# STM32_MACH3-Interfaceboard.net
KiCad netlist of a schematic drawn in EAGLE
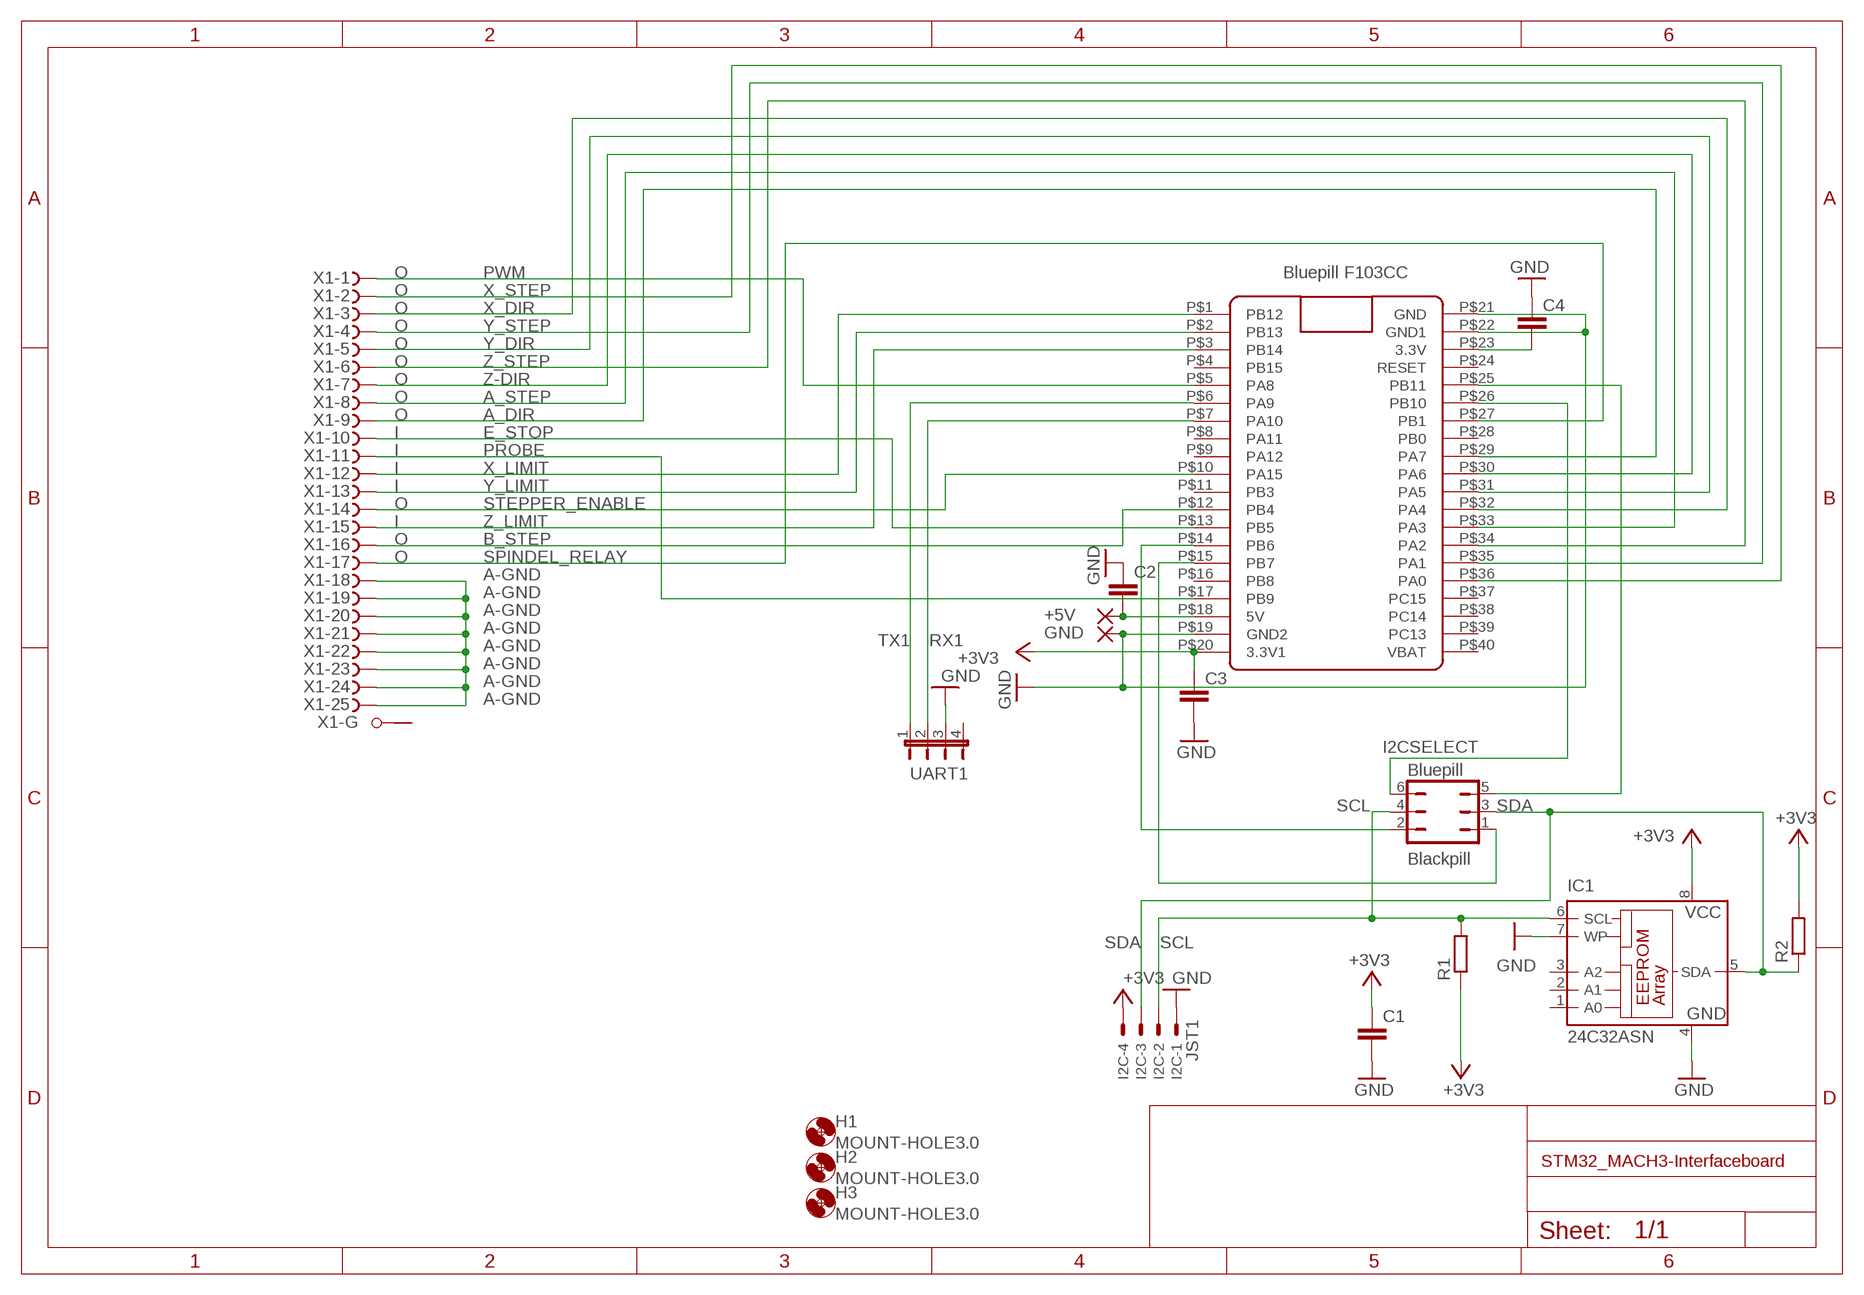
[diagram p0: schematic, sheet 1]

(export (version "E")
  (design (tool "Eeschema 10.0.6"))
  (components
    (comp (ref "+5V")
      (value "2,54/1,0")
      (footprint "eagle-import:2,54_1,0")
      (libsource (lib "eagle-import") (part "2,54/1,0"))
    )
    (comp (ref "C1")
      (value "C-EUC0805")
      (footprint "eagle-import:C0805")
      (libsource (lib "eagle-import") (part "C-EUC0805"))
    )
    (comp (ref "C2")
      (value "C-EUC0805")
      (footprint "eagle-import:C0805")
      (libsource (lib "eagle-import") (part "C-EUC0805"))
    )
    (comp (ref "C3")
      (value "C-EUC0805")
      (footprint "eagle-import:C0805")
      (libsource (lib "eagle-import") (part "C-EUC0805"))
    )
    (comp (ref "C4")
      (value "C-EUC0805")
      (footprint "eagle-import:C0805")
      (libsource (lib "eagle-import") (part "C-EUC0805"))
    )
    (comp (ref "GND")
      (value "2,54/1,0")
      (footprint "eagle-import:2,54_1,0")
      (libsource (lib "eagle-import") (part "2,54/1,0"))
    )
    (comp (ref "H1")
      (value "MOUNT-HOLE3.0")
      (footprint "eagle-import:3,0")
      (libsource (lib "eagle-import") (part "MOUNT-HOLE3.0"))
    )
    (comp (ref "H2")
      (value "MOUNT-HOLE3.0")
      (footprint "eagle-import:3,0")
      (libsource (lib "eagle-import") (part "MOUNT-HOLE3.0"))
    )
    (comp (ref "H3")
      (value "MOUNT-HOLE3.0")
      (footprint "eagle-import:3,0")
      (libsource (lib "eagle-import") (part "MOUNT-HOLE3.0"))
    )
    (comp (ref "I2C")
      (value "JST1")
      (footprint "eagle-import:JST-XH-04-PACKAGE-LONG-PAD")
      (libsource (lib "eagle-import") (part "JST-XH-04-PIN-LONG-PAD"))
    )
    (comp (ref "I2CSELECT")
      (value "JP3Q")
      (footprint "eagle-import:JP3Q")
      (libsource (lib "eagle-import") (part "JP3Q"))
    )
    (comp (ref "IC1")
      (value "24C32ASN")
      (footprint "eagle-import:SO-08")
      (fields (field (name "MPN") "IS24C32A-2GLI"))
      (libsource (lib "eagle-import") (part "24SNC32A"))
    )
    (comp (ref "R1")
      (value "R-EU_R0805")
      (footprint "eagle-import:R0805")
      (libsource (lib "eagle-import") (part "R-EU_R0805"))
    )
    (comp (ref "R2")
      (value "R-EU_R0805")
      (footprint "eagle-import:R0805")
      (libsource (lib "eagle-import") (part "R-EU_R0805"))
    )
    (comp (ref "U$1")
      (value "BLUE_PILL")
      (footprint "eagle-import:BLUE_PILL")
      (libsource (lib "eagle-import") (part "BLUE_PILL"))
    )
    (comp (ref "UART1")
      (value "JP4E")
      (footprint "eagle-import:JP4")
      (libsource (lib "eagle-import") (part "JP4E"))
    )
    (comp (ref "X1")
      (value "F25HPS")
      (footprint "eagle-import:F25HP")
      (libsource (lib "eagle-import") (part "F25HPS"))
    )
  )
  (nets
    (net (code "1") (name "+3V3") (class "Default")
      (node (ref "C1") (pin "1") (pinfunction "1_1") (pintype "passive"))
      (node (ref "C3") (pin "1") (pinfunction "1_1") (pintype "passive"))
      (node (ref "I2C") (pin "4") (pinfunction "S_4") (pintype "passive"))
      (node (ref "IC1") (pin "8") (pinfunction "VCC_8") (pintype "power_in"))
      (node (ref "R1") (pin "1") (pinfunction "1_1") (pintype "passive"))
      (node (ref "R2") (pin "2") (pinfunction "2_2") (pintype "passive"))
      (node (ref "U$1") (pin "P$20") (pinfunction "3.3V1_P$20") (pintype "bidirectional"))
    )
    (net (code "2") (name "/A-GND") (class "Default")
      (node (ref "X1") (pin "18") (pinfunction "F_18") (pintype "passive"))
      (node (ref "X1") (pin "19") (pinfunction "F_19") (pintype "passive"))
      (node (ref "X1") (pin "20") (pinfunction "F_20") (pintype "passive"))
      (node (ref "X1") (pin "21") (pinfunction "F_21") (pintype "passive"))
      (node (ref "X1") (pin "22") (pinfunction "F_22") (pintype "passive"))
      (node (ref "X1") (pin "23") (pinfunction "F_23") (pintype "passive"))
      (node (ref "X1") (pin "24") (pinfunction "F_24") (pintype "passive"))
      (node (ref "X1") (pin "25") (pinfunction "F_25") (pintype "passive"))
    )
    (net (code "3") (name "/A_DIR") (class "Default")
      (node (ref "U$1") (pin "P$29") (pinfunction "PA7_P$29") (pintype "bidirectional"))
      (node (ref "X1") (pin "9") (pinfunction "F_9") (pintype "passive"))
    )
    (net (code "4") (name "/A_STEP") (class "Default")
      (node (ref "U$1") (pin "P$33") (pinfunction "PA3_P$33") (pintype "bidirectional"))
      (node (ref "X1") (pin "8") (pinfunction "F_8") (pintype "passive"))
    )
    (net (code "5") (name "/B_STEP") (class "Default")
      (node (ref "U$1") (pin "P$12") (pinfunction "PB4_P$12") (pintype "bidirectional"))
      (node (ref "X1") (pin "16") (pinfunction "F_16") (pintype "passive"))
    )
    (net (code "6") (name "/E_STOP") (class "Default")
      (node (ref "U$1") (pin "P$13") (pinfunction "PB5_P$13") (pintype "bidirectional"))
      (node (ref "X1") (pin "10") (pinfunction "F_10") (pintype "passive"))
    )
    (net (code "7") (name "/PROBE") (class "Default")
      (node (ref "U$1") (pin "P$17") (pinfunction "PB9_P$17") (pintype "bidirectional"))
      (node (ref "X1") (pin "11") (pinfunction "F_11") (pintype "passive"))
    )
    (net (code "8") (name "/PWM") (class "Default")
      (node (ref "U$1") (pin "P$5") (pinfunction "PA8_P$5") (pintype "bidirectional"))
      (node (ref "X1") (pin "1") (pinfunction "F_1") (pintype "passive"))
    )
    (net (code "9") (name "/RX1") (class "Default")
      (node (ref "U$1") (pin "P$7") (pinfunction "PA10_P$7") (pintype "bidirectional"))
      (node (ref "UART1") (pin "2") (pinfunction "2_2") (pintype "passive"))
    )
    (net (code "10") (name "/SCL") (class "Default")
      (node (ref "I2C") (pin "2") (pinfunction "S_2") (pintype "passive"))
      (node (ref "I2CSELECT") (pin "4") (pinfunction "4_4") (pintype "passive"))
      (node (ref "IC1") (pin "6") (pinfunction "SCL_6") (pintype "input"))
      (node (ref "R1") (pin "2") (pinfunction "2_2") (pintype "passive"))
    )
    (net (code "11") (name "/SDA") (class "Default")
      (node (ref "I2C") (pin "3") (pinfunction "S_3") (pintype "passive"))
      (node (ref "I2CSELECT") (pin "3") (pinfunction "3_3") (pintype "passive"))
      (node (ref "IC1") (pin "5") (pinfunction "SDA_5") (pintype "bidirectional"))
      (node (ref "R2") (pin "1") (pinfunction "1_1") (pintype "passive"))
    )
    (net (code "12") (name "/SPINDEL_RELAY") (class "Default")
      (node (ref "U$1") (pin "P$27") (pinfunction "PB1_P$27") (pintype "bidirectional"))
      (node (ref "X1") (pin "17") (pinfunction "F_17") (pintype "passive"))
    )
    (net (code "13") (name "/STEPPER_ENABLE") (class "Default")
      (node (ref "U$1") (pin "P$10") (pinfunction "PA15_P$10") (pintype "bidirectional"))
      (node (ref "X1") (pin "14") (pinfunction "F_14") (pintype "passive"))
    )
    (net (code "14") (name "/TX1") (class "Default")
      (node (ref "U$1") (pin "P$6") (pinfunction "PA9_P$6") (pintype "bidirectional"))
      (node (ref "UART1") (pin "1") (pinfunction "1_1") (pintype "passive"))
    )
    (net (code "15") (name "/X_DIR") (class "Default")
      (node (ref "U$1") (pin "P$32") (pinfunction "PA4_P$32") (pintype "bidirectional"))
      (node (ref "X1") (pin "3") (pinfunction "F_3") (pintype "passive"))
    )
    (net (code "16") (name "/X_LIMIT") (class "Default")
      (node (ref "U$1") (pin "P$1") (pinfunction "PB12_P$1") (pintype "bidirectional"))
      (node (ref "X1") (pin "12") (pinfunction "F_12") (pintype "passive"))
    )
    (net (code "17") (name "/X_STEP") (class "Default")
      (node (ref "U$1") (pin "P$36") (pinfunction "PA0_P$36") (pintype "bidirectional"))
      (node (ref "X1") (pin "2") (pinfunction "F_2") (pintype "passive"))
    )
    (net (code "18") (name "/Y_DIR") (class "Default")
      (node (ref "U$1") (pin "P$31") (pinfunction "PA5_P$31") (pintype "bidirectional"))
      (node (ref "X1") (pin "5") (pinfunction "F_5") (pintype "passive"))
    )
    (net (code "19") (name "/Y_LIMIT") (class "Default")
      (node (ref "U$1") (pin "P$2") (pinfunction "PB13_P$2") (pintype "bidirectional"))
      (node (ref "X1") (pin "13") (pinfunction "F_13") (pintype "passive"))
    )
    (net (code "20") (name "/Y_STEP") (class "Default")
      (node (ref "U$1") (pin "P$35") (pinfunction "PA1_P$35") (pintype "bidirectional"))
      (node (ref "X1") (pin "4") (pinfunction "F_4") (pintype "passive"))
    )
    (net (code "21") (name "/Z-DIR") (class "Default")
      (node (ref "U$1") (pin "P$30") (pinfunction "PA6_P$30") (pintype "bidirectional"))
      (node (ref "X1") (pin "7") (pinfunction "F_7") (pintype "passive"))
    )
    (net (code "22") (name "/Z_LIMIT") (class "Default")
      (node (ref "U$1") (pin "P$3") (pinfunction "PB14_P$3") (pintype "bidirectional"))
      (node (ref "X1") (pin "15") (pinfunction "F_15") (pintype "passive"))
    )
    (net (code "23") (name "/Z_STEP") (class "Default")
      (node (ref "U$1") (pin "P$34") (pinfunction "PA2_P$34") (pintype "bidirectional"))
      (node (ref "X1") (pin "6") (pinfunction "F_6") (pintype "passive"))
    )
    (net (code "24") (name "GND") (class "Default")
      (node (ref "C1") (pin "2") (pinfunction "2_2") (pintype "passive"))
      (node (ref "C2") (pin "1") (pinfunction "1_1") (pintype "passive"))
      (node (ref "C3") (pin "2") (pinfunction "2_2") (pintype "passive"))
      (node (ref "C4") (pin "1") (pinfunction "1_1") (pintype "passive"))
      (node (ref "GND") (pin "1") (pinfunction "P_1") (pintype "passive"))
      (node (ref "I2C") (pin "1") (pinfunction "S_1") (pintype "passive"))
      (node (ref "IC1") (pin "4") (pinfunction "GND_4") (pintype "power_in"))
      (node (ref "IC1") (pin "7") (pinfunction "WP_7") (pintype "input"))
      (node (ref "U$1") (pin "P$19") (pinfunction "GND2_P$19") (pintype "bidirectional"))
      (node (ref "U$1") (pin "P$21") (pinfunction "GND_P$21") (pintype "power_in"))
      (node (ref "U$1") (pin "P$22") (pinfunction "GND1_P$22") (pintype "bidirectional"))
      (node (ref "UART1") (pin "3") (pinfunction "3_3") (pintype "passive"))
    )
    (net (code "25") (name "Net-(+5V-P)") (class "Default")
      (node (ref "+5V") (pin "1") (pinfunction "P_1") (pintype "passive"))
      (node (ref "C2") (pin "2") (pinfunction "2_2") (pintype "passive"))
      (node (ref "U$1") (pin "P$18") (pinfunction "5V_P$18") (pintype "bidirectional"))
    )
    (net (code "26") (name "Net-(U$1-3.3V)") (class "Default")
      (node (ref "C4") (pin "2") (pinfunction "2_2") (pintype "passive"))
      (node (ref "U$1") (pin "P$23") (pinfunction "3.3V_P$23") (pintype "bidirectional"))
    )
    (net (code "27") (name "Net-(U$1-PB6)") (class "Default")
      (node (ref "I2CSELECT") (pin "2") (pinfunction "2_2") (pintype "passive"))
      (node (ref "U$1") (pin "P$14") (pinfunction "PB6_P$14") (pintype "bidirectional"))
    )
    (net (code "28") (name "Net-(U$1-PB7)") (class "Default")
      (node (ref "I2CSELECT") (pin "1") (pinfunction "1_1") (pintype "passive"))
      (node (ref "U$1") (pin "P$15") (pinfunction "PB7_P$15") (pintype "bidirectional"))
    )
    (net (code "29") (name "Net-(U$1-PB10)") (class "Default")
      (node (ref "I2CSELECT") (pin "6") (pinfunction "6_6") (pintype "passive"))
      (node (ref "U$1") (pin "P$26") (pinfunction "PB10_P$26") (pintype "bidirectional"))
    )
    (net (code "30") (name "Net-(U$1-PB11)") (class "Default")
      (node (ref "I2CSELECT") (pin "5") (pinfunction "5_5") (pintype "passive"))
      (node (ref "U$1") (pin "P$25") (pinfunction "PB11_P$25") (pintype "bidirectional"))
    )
    (net (code "31") (name "unconnected-(IC1-A0-Pad1)") (class "Default")
      (node (ref "IC1") (pin "1") (pinfunction "A0_1") (pintype "input"))
    )
    (net (code "32") (name "unconnected-(IC1-A1-Pad2)") (class "Default")
      (node (ref "IC1") (pin "2") (pinfunction "A1_2") (pintype "input"))
    )
    (net (code "33") (name "unconnected-(IC1-A2-Pad3)") (class "Default")
      (node (ref "IC1") (pin "3") (pinfunction "A2_3") (pintype "input"))
    )
    (net (code "34") (name "unconnected-(U$1-PA11-PadP$8)") (class "Default")
      (node (ref "U$1") (pin "P$8") (pinfunction "PA11_P$8") (pintype "bidirectional"))
    )
    (net (code "35") (name "unconnected-(U$1-PA12-PadP$9)") (class "Default")
      (node (ref "U$1") (pin "P$9") (pinfunction "PA12_P$9") (pintype "bidirectional"))
    )
    (net (code "36") (name "unconnected-(U$1-PB0-PadP$28)") (class "Default")
      (node (ref "U$1") (pin "P$28") (pinfunction "PB0_P$28") (pintype "bidirectional"))
    )
    (net (code "37") (name "unconnected-(U$1-PB3-PadP$11)") (class "Default")
      (node (ref "U$1") (pin "P$11") (pinfunction "PB3_P$11") (pintype "bidirectional"))
    )
    (net (code "38") (name "unconnected-(U$1-PB8-PadP$16)") (class "Default")
      (node (ref "U$1") (pin "P$16") (pinfunction "PB8_P$16") (pintype "bidirectional"))
    )
    (net (code "39") (name "unconnected-(U$1-PB15-PadP$4)") (class "Default")
      (node (ref "U$1") (pin "P$4") (pinfunction "PB15_P$4") (pintype "bidirectional"))
    )
    (net (code "40") (name "unconnected-(U$1-PC13-PadP$39)") (class "Default")
      (node (ref "U$1") (pin "P$39") (pinfunction "PC13_P$39") (pintype "bidirectional"))
    )
    (net (code "41") (name "unconnected-(U$1-PC14-PadP$38)") (class "Default")
      (node (ref "U$1") (pin "P$38") (pinfunction "PC14_P$38") (pintype "bidirectional"))
    )
    (net (code "42") (name "unconnected-(U$1-PC15-PadP$37)") (class "Default")
      (node (ref "U$1") (pin "P$37") (pinfunction "PC15_P$37") (pintype "bidirectional"))
    )
    (net (code "43") (name "unconnected-(U$1-RESET-PadP$24)") (class "Default")
      (node (ref "U$1") (pin "P$24") (pinfunction "RESET_P$24") (pintype "bidirectional"))
    )
    (net (code "44") (name "unconnected-(U$1-VBAT-PadP$40)") (class "Default")
      (node (ref "U$1") (pin "P$40") (pinfunction "VBAT_P$40") (pintype "bidirectional"))
    )
    (net (code "45") (name "unconnected-(UART1-Pad4)") (class "Default")
      (node (ref "UART1") (pin "4") (pinfunction "4_4") (pintype "passive"))
    )
    (net (code "46") (name "unconnected-(X1-PadG1)") (class "Default")
      (node (ref "X1") (pin "G1") (pinfunction "G1_G1") (pintype "passive"))
    )
    (net (code "47") (name "unconnected-(X1-PadG2)") (class "Default")
      (node (ref "X1") (pin "G2") (pinfunction "G2_G2") (pintype "passive"))
    )
  )
)
